# ospi143.net
KiCad netlist of a schematic drawn in EAGLE
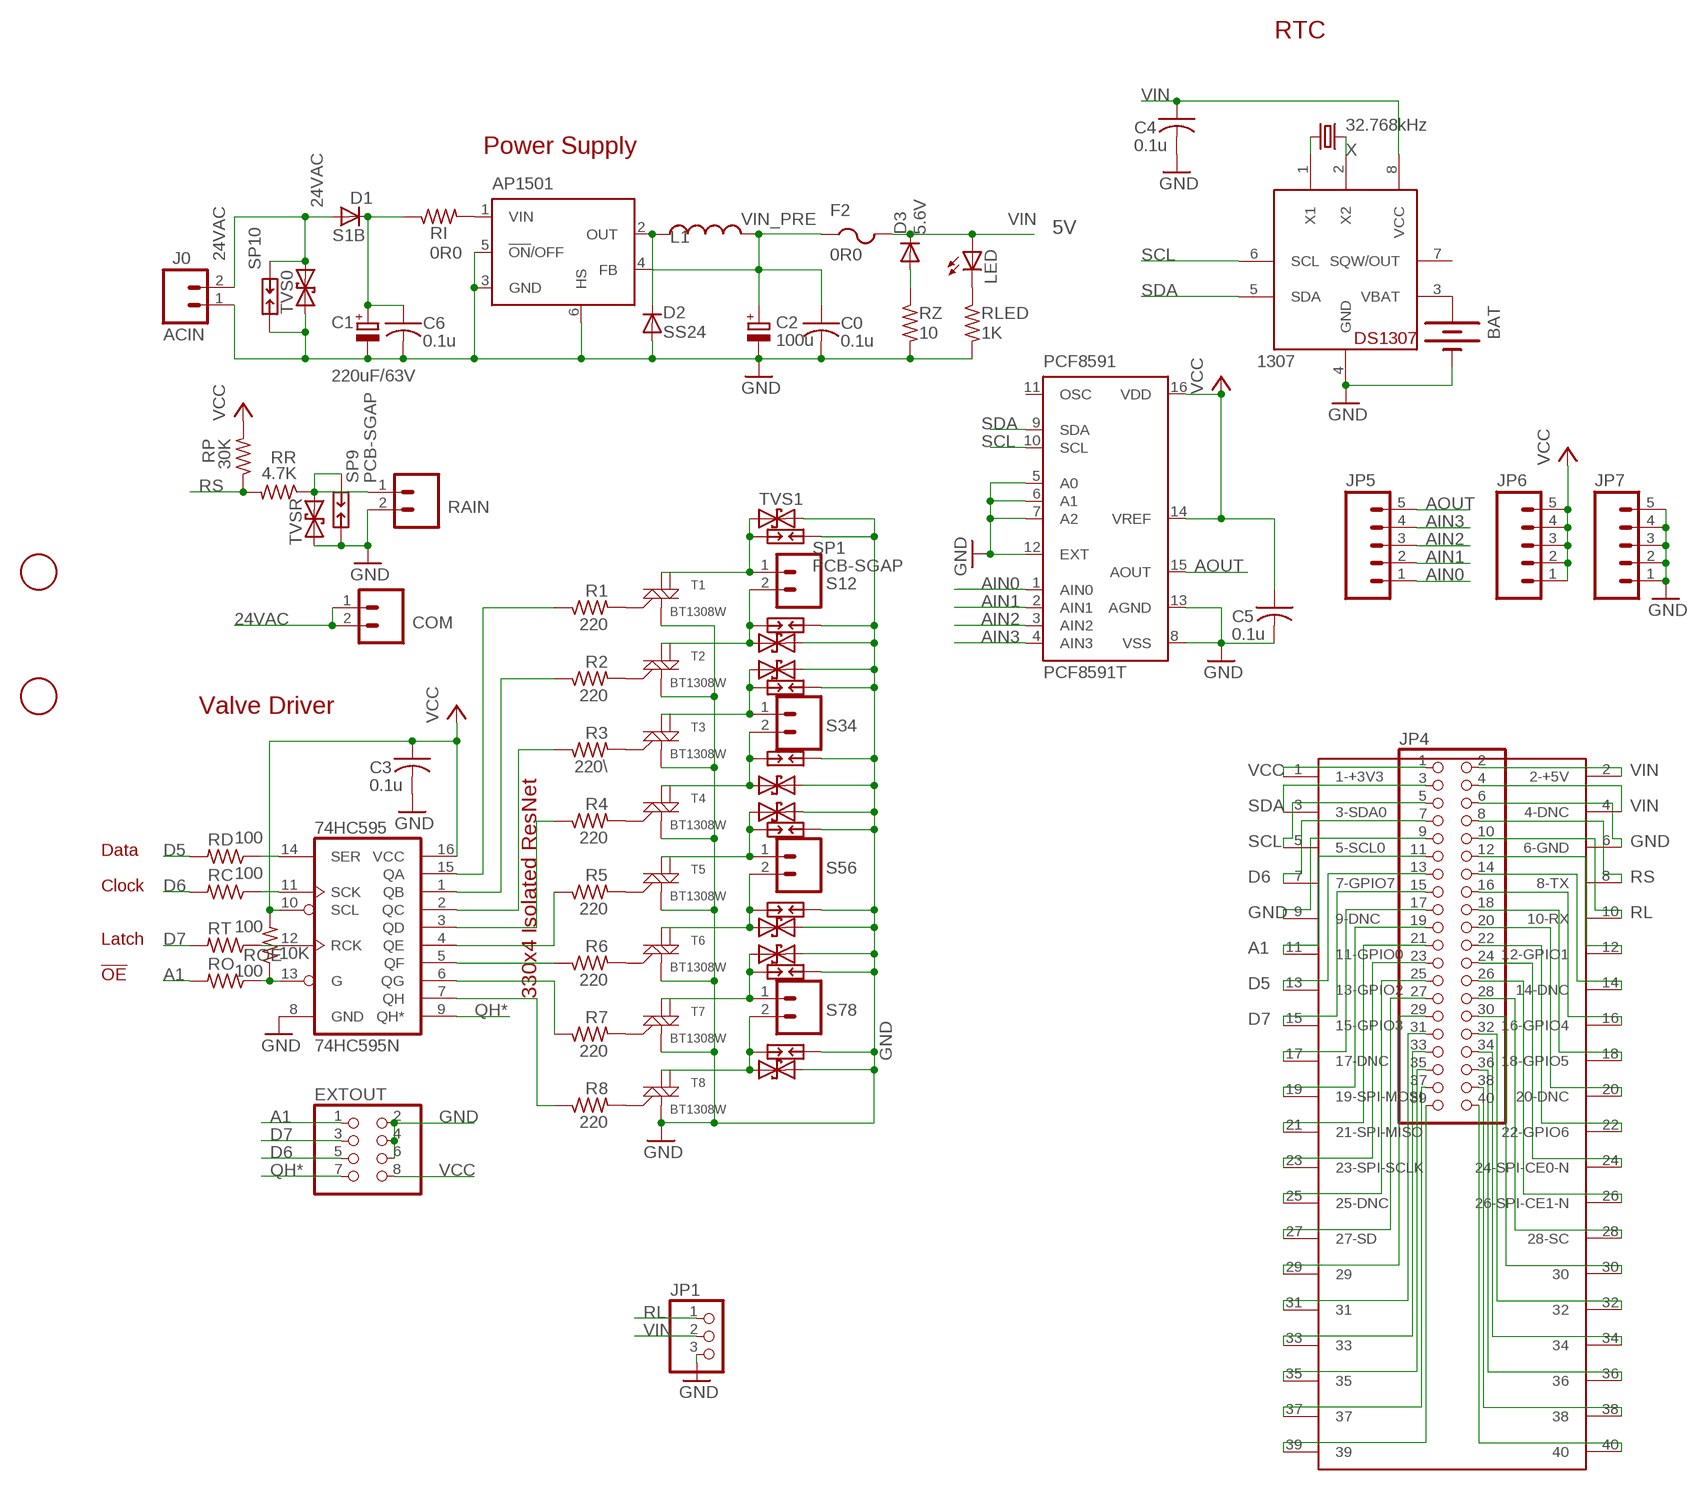
[diagram p0: schematic, sheet 1]

(export (version "E")
  (design (tool "Eeschema 10.0.6"))
  (components
    (comp (ref "74HC595")
      (value "74HC595N")
      (footprint "eagle-import:SO16")
      (libsource (lib "eagle-import") (part "74595DLS"))
    )
    (comp (ref "1307")
      (value "DS1307")
      (footprint "eagle-import:SO08")
      (libsource (lib "eagle-import") (part "DS1307SOIC"))
    )
    (comp (ref "AP1501")
      (value "LM2596S")
      (footprint "eagle-import:TO263-5")
      (fields (field (name "MF") "NATIONAL SEMICONDUCTOR") (field (name "MPN") "LM2596S-ADJ/NOPB"))
      (libsource (lib "eagle-import") (part "LM2596S"))
    )
    (comp (ref "BAT")
      (value "BATTERYBATTERY_12MM_SMT")
      (footprint "eagle-import:BATTCON_12MM_SMT")
      (libsource (lib "eagle-import") (part "BATTERYBATTERY_12MM_SMT"))
    )
    (comp (ref "C0")
      (value "0.1u")
      (footprint "eagle-import:C0603K")
      (libsource (lib "eagle-import") (part "C-USC0603K"))
    )
    (comp (ref "C1")
      (value "220uF/63V")
      (footprint "eagle-import:PANASONIC_E")
      (libsource (lib "eagle-import") (part "CPOL-EUE"))
    )
    (comp (ref "C2")
      (value "100u")
      (footprint "eagle-import:PANASONIC_E")
      (libsource (lib "eagle-import") (part "CPOL-EUE"))
    )
    (comp (ref "C3")
      (value "0.1u")
      (footprint "eagle-import:C0603K")
      (libsource (lib "eagle-import") (part "C-USC0603K"))
    )
    (comp (ref "C4")
      (value "0.1u")
      (footprint "eagle-import:C0603K")
      (libsource (lib "eagle-import") (part "C-USC0603K"))
    )
    (comp (ref "C5")
      (value "0.1u")
      (footprint "eagle-import:C0603K")
      (libsource (lib "eagle-import") (part "C-USC0603K"))
    )
    (comp (ref "C6")
      (value "0.1u")
      (footprint "eagle-import:C0603K")
      (libsource (lib "eagle-import") (part "C-USC0603K"))
    )
    (comp (ref "COM")
      (value "M025MM-X")
      (footprint "eagle-import:SCREWTERMINAL-5MM-2-X")
      (libsource (lib "eagle-import") (part "M025MM-X"))
    )
    (comp (ref "D1")
      (value "S1B")
      (footprint "eagle-import:DO-214AC")
      (libsource (lib "eagle-import") (part "DIODE-DO-214AC"))
    )
    (comp (ref "D2")
      (value "SS24")
      (footprint "eagle-import:SMB")
      (libsource (lib "eagle-import") (part "DIODE-SMB"))
    )
    (comp (ref "D3")
      (value "5.6V")
      (footprint "eagle-import:MINIMELF")
      (libsource (lib "eagle-import") (part "DIODE-MINIMELF"))
    )
    (comp (ref "EXTOUT")
      (value "PINHD-2X4/90")
      (footprint "eagle-import:2X04_90")
      (libsource (lib "eagle-import") (part "PINHD-2X4/90"))
    )
    (comp (ref "F2")
      (value "0R0")
      (footprint "eagle-import:1812")
      (libsource (lib "eagle-import") (part "PTCFUSE-1812"))
    )
    (comp (ref "J0")
      (value "ACIN")
      (footprint "eagle-import:SCREWTERMINAL-4MM-2-X")
      (libsource (lib "eagle-import") (part "M024MM-X"))
    )
    (comp (ref "JP1")
      (value "PINHD-1X3")
      (footprint "eagle-import:1X03")
      (libsource (lib "eagle-import") (part "PINHD-1X3"))
    )
    (comp (ref "JP4")
      (value "PINHD-2X20")
      (footprint "eagle-import:2X20")
      (libsource (lib "eagle-import") (part "PINHD-2X20"))
    )
    (comp (ref "JP5")
      (value "M05PTH")
      (footprint "eagle-import:1X05")
      (libsource (lib "eagle-import") (part "M05PTH"))
    )
    (comp (ref "JP6")
      (value "M05PTH")
      (footprint "eagle-import:1X05")
      (libsource (lib "eagle-import") (part "M05PTH"))
    )
    (comp (ref "JP7")
      (value "M05PTH")
      (footprint "eagle-import:1X05")
      (libsource (lib "eagle-import") (part "M05PTH"))
    )
    (comp (ref "L1")
      (value "150uH")
      (footprint "eagle-import:CDRH125")
      (libsource (lib "eagle-import") (part "INDUCTORPWR"))
    )
    (comp (ref "LED")
      (value "LEDCHIPLED_0805")
      (footprint "eagle-import:CHIPLED_0805")
      (libsource (lib "eagle-import") (part "LEDCHIPLED_0805"))
    )
    (comp (ref "PCF8591")
      (value "PCF8591T")
      (footprint "eagle-import:SO16W")
      (fields (field (name "MPN") "PCF8591T/2,512"))
      (libsource (lib "eagle-import") (part "PCF8591T"))
    )
    (comp (ref "R1")
      (value "220")
      (footprint "eagle-import:R0603")
      (libsource (lib "eagle-import") (part "R-US_R0603"))
    )
    (comp (ref "R2")
      (value "220")
      (footprint "eagle-import:R0603")
      (libsource (lib "eagle-import") (part "R-US_R0603"))
    )
    (comp (ref "R3")
      (value "220\\")
      (footprint "eagle-import:R0603")
      (libsource (lib "eagle-import") (part "R-US_R0603"))
    )
    (comp (ref "R4")
      (value "220")
      (footprint "eagle-import:R0603")
      (libsource (lib "eagle-import") (part "R-US_R0603"))
    )
    (comp (ref "R5")
      (value "220")
      (footprint "eagle-import:R0603")
      (libsource (lib "eagle-import") (part "R-US_R0603"))
    )
    (comp (ref "R6")
      (value "220")
      (footprint "eagle-import:R0603")
      (libsource (lib "eagle-import") (part "R-US_R0603"))
    )
    (comp (ref "R7")
      (value "220")
      (footprint "eagle-import:R0603")
      (libsource (lib "eagle-import") (part "R-US_R0603"))
    )
    (comp (ref "R8")
      (value "220")
      (footprint "eagle-import:R0603")
      (libsource (lib "eagle-import") (part "R-US_R0603"))
    )
    (comp (ref "RAIN")
      (value "M025MM-X")
      (footprint "eagle-import:SCREWTERMINAL-5MM-2-X")
      (libsource (lib "eagle-import") (part "M025MM-X"))
    )
    (comp (ref "RC")
      (value "100")
      (footprint "eagle-import:R0603")
      (libsource (lib "eagle-import") (part "R-US_R0603"))
    )
    (comp (ref "RD")
      (value "100")
      (footprint "eagle-import:R0603")
      (libsource (lib "eagle-import") (part "R-US_R0603"))
    )
    (comp (ref "RI")
      (value "0R0")
      (footprint "eagle-import:R2010")
      (libsource (lib "eagle-import") (part "adafruitGood_R-US_R2010"))
    )
    (comp (ref "RLED")
      (value "1K")
      (footprint "eagle-import:R0805")
      (libsource (lib "eagle-import") (part "R-US_R0805"))
    )
    (comp (ref "RO")
      (value "100")
      (footprint "eagle-import:R0603")
      (libsource (lib "eagle-import") (part "R-US_R0603"))
    )
    (comp (ref "ROE")
      (value "10K")
      (footprint "eagle-import:R0603")
      (libsource (lib "eagle-import") (part "R-US_R0603"))
    )
    (comp (ref "RP")
      (value "30K")
      (footprint "eagle-import:R0805")
      (libsource (lib "eagle-import") (part "R-US_R0805"))
    )
    (comp (ref "RR")
      (value "4.7K")
      (footprint "eagle-import:R0805")
      (libsource (lib "eagle-import") (part "R-US_R0805"))
    )
    (comp (ref "RT")
      (value "100")
      (footprint "eagle-import:R0603")
      (libsource (lib "eagle-import") (part "R-US_R0603"))
    )
    (comp (ref "RZ")
      (value "10")
      (footprint "eagle-import:R2010")
      (libsource (lib "eagle-import") (part "R-US_R2010"))
    )
    (comp (ref "S12")
      (value "M025MM-X")
      (footprint "eagle-import:SCREWTERMINAL-5MM-2-X")
      (libsource (lib "eagle-import") (part "M025MM-X"))
    )
    (comp (ref "S34")
      (value "M025MM-X")
      (footprint "eagle-import:SCREWTERMINAL-5MM-2-X")
      (libsource (lib "eagle-import") (part "M025MM-X"))
    )
    (comp (ref "S56")
      (value "M025MM-X")
      (footprint "eagle-import:SCREWTERMINAL-5MM-2-X")
      (libsource (lib "eagle-import") (part "M025MM-X"))
    )
    (comp (ref "S78")
      (value "M025MM-X")
      (footprint "eagle-import:SCREWTERMINAL-5MM-2-X")
      (libsource (lib "eagle-import") (part "M025MM-X"))
    )
    (comp (ref "SP1")
      (value "PCB-SGAP")
      (footprint "eagle-import:PCB-SGAP")
      (libsource (lib "eagle-import") (part "PCB-SGAP"))
    )
    (comp (ref "SP2")
      (value "PCB-SGAP")
      (footprint "eagle-import:PCB-SGAP")
      (libsource (lib "eagle-import") (part "PCB-SGAP"))
    )
    (comp (ref "SP3")
      (value "PCB-SGAP")
      (footprint "eagle-import:PCB-SGAP")
      (libsource (lib "eagle-import") (part "PCB-SGAP"))
    )
    (comp (ref "SP4")
      (value "PCB-SGAP")
      (footprint "eagle-import:PCB-SGAP")
      (libsource (lib "eagle-import") (part "PCB-SGAP"))
    )
    (comp (ref "SP5")
      (value "PCB-SGAP")
      (footprint "eagle-import:PCB-SGAP")
      (libsource (lib "eagle-import") (part "PCB-SGAP"))
    )
    (comp (ref "SP6")
      (value "PCB-SGAP")
      (footprint "eagle-import:PCB-SGAP")
      (libsource (lib "eagle-import") (part "PCB-SGAP"))
    )
    (comp (ref "SP7")
      (value "PCB-SGAP")
      (footprint "eagle-import:PCB-SGAP")
      (libsource (lib "eagle-import") (part "PCB-SGAP"))
    )
    (comp (ref "SP8")
      (value "PCB-SGAP")
      (footprint "eagle-import:PCB-SGAP")
      (libsource (lib "eagle-import") (part "PCB-SGAP"))
    )
    (comp (ref "SP9")
      (value "PCB-SGAP")
      (footprint "eagle-import:PCB-SGAP")
      (libsource (lib "eagle-import") (part "PCB-SGAP"))
    )
    (comp (ref "SP10")
      (value "PCB-SGAP")
      (footprint "eagle-import:PCB-SGAP")
      (libsource (lib "eagle-import") (part "PCB-SGAP"))
    )
    (comp (ref "T1")
      (value "BT1308W")
      (footprint "eagle-import:SOT223")
      (libsource (lib "eagle-import") (part "MAC97SOT223"))
    )
    (comp (ref "T2")
      (value "BT1308W")
      (footprint "eagle-import:SOT223")
      (libsource (lib "eagle-import") (part "MAC97SOT223"))
    )
    (comp (ref "T3")
      (value "BT1308W")
      (footprint "eagle-import:SOT223")
      (libsource (lib "eagle-import") (part "MAC97SOT223"))
    )
    (comp (ref "T4")
      (value "BT1308W")
      (footprint "eagle-import:SOT223")
      (libsource (lib "eagle-import") (part "MAC97SOT223"))
    )
    (comp (ref "T5")
      (value "BT1308W")
      (footprint "eagle-import:SOT223")
      (libsource (lib "eagle-import") (part "MAC97SOT223"))
    )
    (comp (ref "T6")
      (value "BT1308W")
      (footprint "eagle-import:SOT223")
      (libsource (lib "eagle-import") (part "MAC97SOT223"))
    )
    (comp (ref "T7")
      (value "BT1308W")
      (footprint "eagle-import:SOT223")
      (libsource (lib "eagle-import") (part "MAC97SOT223"))
    )
    (comp (ref "T8")
      (value "BT1308W")
      (footprint "eagle-import:SOT223")
      (libsource (lib "eagle-import") (part "MAC97SOT223"))
    )
    (comp (ref "TVS0")
      (value "TVSSMB")
      (footprint "eagle-import:SMB")
      (libsource (lib "eagle-import") (part "TVSSMB"))
    )
    (comp (ref "TVS1")
      (value "TVSSMB")
      (footprint "eagle-import:SMB")
      (libsource (lib "eagle-import") (part "TVSSMB"))
    )
    (comp (ref "TVS2")
      (value "TVSSMB")
      (footprint "eagle-import:SMB")
      (libsource (lib "eagle-import") (part "TVSSMB"))
    )
    (comp (ref "TVS3")
      (value "TVSSMB")
      (footprint "eagle-import:SMB")
      (libsource (lib "eagle-import") (part "TVSSMB"))
    )
    (comp (ref "TVS4")
      (value "TVSSMB")
      (footprint "eagle-import:SMB")
      (libsource (lib "eagle-import") (part "TVSSMB"))
    )
    (comp (ref "TVS5")
      (value "TVSSMB")
      (footprint "eagle-import:SMB")
      (libsource (lib "eagle-import") (part "TVSSMB"))
    )
    (comp (ref "TVS6")
      (value "TVSSMB")
      (footprint "eagle-import:SMB")
      (libsource (lib "eagle-import") (part "TVSSMB"))
    )
    (comp (ref "TVS7")
      (value "TVSSMB")
      (footprint "eagle-import:SMB")
      (libsource (lib "eagle-import") (part "TVSSMB"))
    )
    (comp (ref "TVS8")
      (value "TVSSMB")
      (footprint "eagle-import:SMB")
      (libsource (lib "eagle-import") (part "TVSSMB"))
    )
    (comp (ref "TVSR")
      (value "TVSSMB")
      (footprint "eagle-import:SMB")
      (libsource (lib "eagle-import") (part "TVSSMB"))
    )
    (comp (ref "U$1")
      (value "FIDUCIAL")
      (footprint "eagle-import:FIDUCIAL_1MM")
      (libsource (lib "eagle-import") (part "FIDUCIAL"))
    )
    (comp (ref "U$2")
      (value "RPIB+")
      (footprint "eagle-import:RPIB+")
      (libsource (lib "eagle-import") (part "RPIB+"))
    )
    (comp (ref "U$3")
      (value "FIDUCIAL")
      (footprint "eagle-import:FIDUCIAL_1MM")
      (libsource (lib "eagle-import") (part "FIDUCIAL"))
    )
    (comp (ref "X")
      (value "32.768kHz")
      (footprint "eagle-import:MM20SS")
      (libsource (lib "eagle-import") (part "CRYSTALMM20SS"))
    )
  )
  (nets
    (net (code "1") (name "/24VAC") (class "Default")
      (node (ref "COM") (pin "1") (pinfunction "1_1") (pintype "passive"))
      (node (ref "COM") (pin "2") (pinfunction "2_2") (pintype "passive"))
      (node (ref "D1") (pin "A") (pinfunction "A_A") (pintype "passive"))
      (node (ref "J0") (pin "2") (pinfunction "2_2") (pintype "passive"))
      (node (ref "SP10") (pin "1") (pinfunction "1_1") (pintype "passive"))
      (node (ref "TVS0") (pin "C") (pinfunction "C_C") (pintype "passive"))
    )
    (net (code "2") (name "/A1") (class "Default")
      (node (ref "EXTOUT") (pin "1") (pinfunction "1_1") (pintype "passive"))
      (node (ref "JP4") (pin "11") (pinfunction "11_11") (pintype "passive"))
      (node (ref "RO") (pin "2") (pinfunction "2_2") (pintype "passive"))
      (node (ref "U$2") (pin "11") (pinfunction "11-GPIO0_11") (pintype "bidirectional"))
    )
    (net (code "3") (name "/AIN0") (class "Default")
      (node (ref "JP5") (pin "1") (pinfunction "1_1") (pintype "passive"))
      (node (ref "PCF8591") (pin "1") (pinfunction "AIN0_1") (pintype "input"))
    )
    (net (code "4") (name "/AIN1") (class "Default")
      (node (ref "JP5") (pin "2") (pinfunction "2_2") (pintype "passive"))
      (node (ref "PCF8591") (pin "2") (pinfunction "AIN1_2") (pintype "input"))
    )
    (net (code "5") (name "/AIN2") (class "Default")
      (node (ref "JP5") (pin "3") (pinfunction "3_3") (pintype "passive"))
      (node (ref "PCF8591") (pin "3") (pinfunction "AIN2_3") (pintype "input"))
    )
    (net (code "6") (name "/AIN3") (class "Default")
      (node (ref "JP5") (pin "4") (pinfunction "4_4") (pintype "passive"))
      (node (ref "PCF8591") (pin "4") (pinfunction "AIN3_4") (pintype "input"))
    )
    (net (code "7") (name "/AOUT") (class "Default")
      (node (ref "JP5") (pin "5") (pinfunction "5_5") (pintype "passive"))
      (node (ref "PCF8591") (pin "15") (pinfunction "AOUT_15") (pintype "output"))
    )
    (net (code "8") (name "/D5") (class "Default")
      (node (ref "JP4") (pin "13") (pinfunction "13_13") (pintype "passive"))
      (node (ref "RD") (pin "2") (pinfunction "2_2") (pintype "passive"))
      (node (ref "U$2") (pin "13") (pinfunction "13-GPIO2_13") (pintype "bidirectional"))
    )
    (net (code "9") (name "/D6") (class "Default")
      (node (ref "EXTOUT") (pin "5") (pinfunction "5_5") (pintype "passive"))
      (node (ref "JP4") (pin "7") (pinfunction "7_7") (pintype "passive"))
      (node (ref "RC") (pin "2") (pinfunction "2_2") (pintype "passive"))
      (node (ref "U$2") (pin "7") (pinfunction "7-GPIO7_7") (pintype "bidirectional"))
    )
    (net (code "10") (name "/D7") (class "Default")
      (node (ref "EXTOUT") (pin "3") (pinfunction "3_3") (pintype "passive"))
      (node (ref "JP4") (pin "15") (pinfunction "15_15") (pintype "passive"))
      (node (ref "RT") (pin "2") (pinfunction "2_2") (pintype "passive"))
      (node (ref "U$2") (pin "15") (pinfunction "15-GPIO3_15") (pintype "bidirectional"))
    )
    (net (code "11") (name "/QH*") (class "Default")
      (node (ref "74HC595") (pin "9") (pinfunction "QH*_9") (pintype "tri_state"))
      (node (ref "EXTOUT") (pin "7") (pinfunction "7_7") (pintype "passive"))
    )
    (net (code "12") (name "/RL") (class "Default")
      (node (ref "JP1") (pin "1") (pinfunction "1_1") (pintype "passive"))
      (node (ref "JP4") (pin "10") (pinfunction "10_10") (pintype "passive"))
      (node (ref "U$2") (pin "10") (pinfunction "10-RX_10") (pintype "bidirectional"))
    )
    (net (code "13") (name "/RS") (class "Default")
      (node (ref "JP4") (pin "8") (pinfunction "8_8") (pintype "passive"))
      (node (ref "RP") (pin "1") (pinfunction "1_1") (pintype "passive"))
      (node (ref "RR") (pin "2") (pinfunction "2_2") (pintype "passive"))
      (node (ref "U$2") (pin "8") (pinfunction "8-TX_8") (pintype "bidirectional"))
    )
    (net (code "14") (name "/SCL") (class "Default")
      (node (ref "1307") (pin "6") (pinfunction "SCL_6") (pintype "bidirectional"))
      (node (ref "JP4") (pin "5") (pinfunction "5_5") (pintype "passive"))
      (node (ref "PCF8591") (pin "10") (pinfunction "SCL_10") (pintype "input"))
      (node (ref "U$2") (pin "5") (pinfunction "5-SCL0_5") (pintype "bidirectional"))
    )
    (net (code "15") (name "/SDA") (class "Default")
      (node (ref "1307") (pin "5") (pinfunction "SDA_5") (pintype "bidirectional"))
      (node (ref "JP4") (pin "3") (pinfunction "3_3") (pintype "passive"))
      (node (ref "PCF8591") (pin "9") (pinfunction "SDA_9") (pintype "bidirectional"))
      (node (ref "U$2") (pin "3") (pinfunction "3-SDA0_3") (pintype "bidirectional"))
    )
    (net (code "16") (name "/VIN") (class "Default")
      (node (ref "1307") (pin "8") (pinfunction "VCC_8") (pintype "power_in"))
      (node (ref "C4") (pin "1") (pinfunction "1_1") (pintype "passive"))
      (node (ref "D3") (pin "C") (pinfunction "C_C") (pintype "passive"))
      (node (ref "F2") (pin "2") (pinfunction "2_2") (pintype "passive"))
      (node (ref "JP1") (pin "2") (pinfunction "2_2") (pintype "passive"))
      (node (ref "JP4") (pin "2") (pinfunction "2_2") (pintype "passive"))
      (node (ref "JP4") (pin "4") (pinfunction "4_4") (pintype "passive"))
      (node (ref "LED") (pin "A") (pinfunction "A_A") (pintype "passive"))
      (node (ref "U$2") (pin "2") (pinfunction "2-+5V_2") (pintype "bidirectional"))
      (node (ref "U$2") (pin "4") (pinfunction "4-DNC_4") (pintype "bidirectional"))
    )
    (net (code "17") (name "/VIN_PRE") (class "Default")
      (node (ref "AP1501") (pin "4") (pinfunction "FB_4") (pintype "input"))
      (node (ref "C0") (pin "1") (pinfunction "1_1") (pintype "passive"))
      (node (ref "C2") (pin "+") (pinfunction "+_+") (pintype "passive"))
      (node (ref "F2") (pin "1") (pinfunction "1_1") (pintype "passive"))
      (node (ref "L1") (pin "2") (pinfunction "2_2") (pintype "passive"))
    )
    (net (code "18") (name "GND") (class "Default")
      (node (ref "1307") (pin "4") (pinfunction "GND_4") (pintype "power_in"))
      (node (ref "74HC595") (pin "8") (pinfunction "GND_8") (pintype "power_in"))
      (node (ref "AP1501") (pin "3") (pinfunction "GND_3") (pintype "power_in"))
      (node (ref "AP1501") (pin "5") (pinfunction "~{ON}/OFF_5") (pintype "input"))
      (node (ref "AP1501") (pin "6") (pinfunction "HS_6") (pintype "power_in"))
      (node (ref "BAT") (pin "P$1") (pinfunction "-_P$1") (pintype "power_in"))
      (node (ref "C0") (pin "2") (pinfunction "2_2") (pintype "passive"))
      (node (ref "C1") (pin "-") (pinfunction "-_-") (pintype "passive"))
      (node (ref "C2") (pin "-") (pinfunction "-_-") (pintype "passive"))
      (node (ref "C3") (pin "2") (pinfunction "2_2") (pintype "passive"))
      (node (ref "C4") (pin "2") (pinfunction "2_2") (pintype "passive"))
      (node (ref "C5") (pin "2") (pinfunction "2_2") (pintype "passive"))
      (node (ref "C6") (pin "2") (pinfunction "2_2") (pintype "passive"))
      (node (ref "D2") (pin "A") (pinfunction "A_A") (pintype "passive"))
      (node (ref "EXTOUT") (pin "2") (pinfunction "2_2") (pintype "passive"))
      (node (ref "EXTOUT") (pin "4") (pinfunction "4_4") (pintype "passive"))
      (node (ref "EXTOUT") (pin "6") (pinfunction "6_6") (pintype "passive"))
      (node (ref "J0") (pin "1") (pinfunction "1_1") (pintype "passive"))
      (node (ref "JP1") (pin "3") (pinfunction "3_3") (pintype "passive"))
      (node (ref "JP4") (pin "6") (pinfunction "6_6") (pintype "passive"))
      (node (ref "JP4") (pin "9") (pinfunction "9_9") (pintype "passive"))
      (node (ref "JP7") (pin "1") (pinfunction "1_1") (pintype "passive"))
      (node (ref "JP7") (pin "2") (pinfunction "2_2") (pintype "passive"))
      (node (ref "JP7") (pin "3") (pinfunction "3_3") (pintype "passive"))
      (node (ref "JP7") (pin "4") (pinfunction "4_4") (pintype "passive"))
      (node (ref "JP7") (pin "5") (pinfunction "5_5") (pintype "passive"))
      (node (ref "PCF8591") (pin "12") (pinfunction "EXT_12") (pintype "input"))
      (node (ref "PCF8591") (pin "13") (pinfunction "AGND_13") (pintype "power_in"))
      (node (ref "PCF8591") (pin "5") (pinfunction "A0_5") (pintype "input"))
      (node (ref "PCF8591") (pin "6") (pinfunction "A1_6") (pintype "input"))
      (node (ref "PCF8591") (pin "7") (pinfunction "A2_7") (pintype "input"))
      (node (ref "PCF8591") (pin "8") (pinfunction "VSS_8") (pintype "power_in"))
      (node (ref "RAIN") (pin "2") (pinfunction "2_2") (pintype "passive"))
      (node (ref "RLED") (pin "2") (pinfunction "2_2") (pintype "passive"))
      (node (ref "RZ") (pin "2") (pinfunction "2_2") (pintype "passive"))
      (node (ref "SP1") (pin "1") (pinfunction "1_1") (pintype "passive"))
      (node (ref "SP10") (pin "2") (pinfunction "2_2") (pintype "passive"))
      (node (ref "SP2") (pin "1") (pinfunction "1_1") (pintype "passive"))
      (node (ref "SP3") (pin "1") (pinfunction "1_1") (pintype "passive"))
      (node (ref "SP4") (pin "1") (pinfunction "1_1") (pintype "passive"))
      (node (ref "SP5") (pin "1") (pinfunction "1_1") (pintype "passive"))
      (node (ref "SP6") (pin "1") (pinfunction "1_1") (pintype "passive"))
      (node (ref "SP7") (pin "1") (pinfunction "1_1") (pintype "passive"))
      (node (ref "SP8") (pin "1") (pinfunction "1_1") (pintype "passive"))
      (node (ref "SP9") (pin "2") (pinfunction "2_2") (pintype "passive"))
      (node (ref "T1") (pin "1") (pinfunction "M1_1") (pintype "bidirectional"))
      (node (ref "T2") (pin "1") (pinfunction "M1_1") (pintype "bidirectional"))
      (node (ref "T3") (pin "1") (pinfunction "M1_1") (pintype "bidirectional"))
      (node (ref "T4") (pin "1") (pinfunction "M1_1") (pintype "bidirectional"))
      (node (ref "T5") (pin "1") (pinfunction "M1_1") (pintype "bidirectional"))
      (node (ref "T6") (pin "1") (pinfunction "M1_1") (pintype "bidirectional"))
      (node (ref "T7") (pin "1") (pinfunction "M1_1") (pintype "bidirectional"))
      (node (ref "T8") (pin "1") (pinfunction "M1_1") (pintype "bidirectional"))
      (node (ref "TVS0") (pin "A") (pinfunction "A_A") (pintype "passive"))
      (node (ref "TVS1") (pin "C") (pinfunction "C_C") (pintype "passive"))
      (node (ref "TVS2") (pin "C") (pinfunction "C_C") (pintype "passive"))
      (node (ref "TVS3") (pin "C") (pinfunction "C_C") (pintype "passive"))
      (node (ref "TVS4") (pin "C") (pinfunction "C_C") (pintype "passive"))
      (node (ref "TVS5") (pin "C") (pinfunction "C_C") (pintype "passive"))
      (node (ref "TVS6") (pin "C") (pinfunction "C_C") (pintype "passive"))
      (node (ref "TVS7") (pin "C") (pinfunction "C_C") (pintype "passive"))
      (node (ref "TVS8") (pin "C") (pinfunction "C_C") (pintype "passive"))
      (node (ref "TVSR") (pin "A") (pinfunction "A_A") (pintype "passive"))
      (node (ref "U$2") (pin "6") (pinfunction "6-GND_6") (pintype "bidirectional"))
      (node (ref "U$2") (pin "9") (pinfunction "9-DNC_9") (pintype "bidirectional"))
    )
    (net (code "19") (name "Net-(74HC595-G)") (class "Default")
      (node (ref "74HC595") (pin "13") (pinfunction "G_13") (pintype "input"))
      (node (ref "RO") (pin "1") (pinfunction "1_1") (pintype "passive"))
      (node (ref "ROE") (pin "1") (pinfunction "1_1") (pintype "passive"))
    )
    (net (code "20") (name "Net-(74HC595-QA)") (class "Default")
      (node (ref "74HC595") (pin "15") (pinfunction "QA_15") (pintype "tri_state"))
      (node (ref "R1") (pin "1") (pinfunction "1_1") (pintype "passive"))
    )
    (net (code "21") (name "Net-(74HC595-QB)") (class "Default")
      (node (ref "74HC595") (pin "1") (pinfunction "QB_1") (pintype "tri_state"))
      (node (ref "R2") (pin "1") (pinfunction "1_1") (pintype "passive"))
    )
    (net (code "22") (name "Net-(74HC595-QC)") (class "Default")
      (node (ref "74HC595") (pin "2") (pinfunction "QC_2") (pintype "tri_state"))
      (node (ref "R3") (pin "1") (pinfunction "1_1") (pintype "passive"))
    )
    (net (code "23") (name "Net-(74HC595-QD)") (class "Default")
      (node (ref "74HC595") (pin "3") (pinfunction "QD_3") (pintype "tri_state"))
      (node (ref "R4") (pin "1") (pinfunction "1_1") (pintype "passive"))
    )
    (net (code "24") (name "Net-(74HC595-QE)") (class "Default")
      (node (ref "74HC595") (pin "4") (pinfunction "QE_4") (pintype "tri_state"))
      (node (ref "R5") (pin "1") (pinfunction "1_1") (pintype "passive"))
    )
    (net (code "25") (name "Net-(74HC595-QF)") (class "Default")
      (node (ref "74HC595") (pin "5") (pinfunction "QF_5") (pintype "tri_state"))
      (node (ref "R6") (pin "1") (pinfunction "1_1") (pintype "passive"))
    )
    (net (code "26") (name "Net-(74HC595-QG)") (class "Default")
      (node (ref "74HC595") (pin "6") (pinfunction "QG_6") (pintype "tri_state"))
      (node (ref "R7") (pin "1") (pinfunction "1_1") (pintype "passive"))
    )
    (net (code "27") (name "Net-(74HC595-QH)") (class "Default")
      (node (ref "74HC595") (pin "7") (pinfunction "QH_7") (pintype "tri_state"))
      (node (ref "R8") (pin "1") (pinfunction "1_1") (pintype "passive"))
    )
    (net (code "28") (name "Net-(74HC595-RCK)") (class "Default")
      (node (ref "74HC595") (pin "12") (pinfunction "RCK_12") (pintype "input"))
      (node (ref "RT") (pin "1") (pinfunction "1_1") (pintype "passive"))
    )
    (net (code "29") (name "Net-(74HC595-SCK)") (class "Default")
      (node (ref "74HC595") (pin "11") (pinfunction "SCK_11") (pintype "input"))
      (node (ref "RC") (pin "1") (pinfunction "1_1") (pintype "passive"))
    )
    (net (code "30") (name "Net-(74HC595-SER)") (class "Default")
      (node (ref "74HC595") (pin "14") (pinfunction "SER_14") (pintype "input"))
      (node (ref "RD") (pin "1") (pinfunction "1_1") (pintype "passive"))
    )
    (net (code "31") (name "Net-(1307-VBAT)") (class "Default")
      (node (ref "1307") (pin "3") (pinfunction "VBAT_3") (pintype "power_in"))
      (node (ref "BAT") (pin "P$2") (pinfunction "+_P$2") (pintype "power_in"))
    )
    (net (code "32") (name "Net-(1307-X1)") (class "Default")
      (node (ref "1307") (pin "1") (pinfunction "X1_1") (pintype "passive"))
      (node (ref "X") (pin "1") (pinfunction "1_1") (pintype "passive"))
    )
    (net (code "33") (name "Net-(1307-X2)") (class "Default")
      (node (ref "1307") (pin "2") (pinfunction "X2_2") (pintype "passive"))
      (node (ref "X") (pin "4") (pinfunction "2_4") (pintype "passive"))
    )
    (net (code "34") (name "Net-(AP1501-OUT)") (class "Default")
      (node (ref "AP1501") (pin "2") (pinfunction "OUT_2") (pintype "output"))
      (node (ref "D2") (pin "C") (pinfunction "C_C") (pintype "passive"))
      (node (ref "L1") (pin "1") (pinfunction "1_1") (pintype "passive"))
    )
    (net (code "35") (name "Net-(AP1501-VIN)") (class "Default")
      (node (ref "AP1501") (pin "1") (pinfunction "VIN_1") (pintype "input"))
      (node (ref "RI") (pin "2") (pinfunction "2_2") (pintype "passive"))
    )
    (net (code "36") (name "Net-(C1-Pad+)") (class "Default")
      (node (ref "C1") (pin "+") (pinfunction "+_+") (pintype "passive"))
      (node (ref "C6") (pin "1") (pinfunction "1_1") (pintype "passive"))
      (node (ref "D1") (pin "C") (pinfunction "C_C") (pintype "passive"))
      (node (ref "RI") (pin "1") (pinfunction "1_1") (pintype "passive"))
    )
    (net (code "37") (name "Net-(D3-PadA)") (class "Default")
      (node (ref "D3") (pin "A") (pinfunction "A_A") (pintype "passive"))
      (node (ref "RZ") (pin "1") (pinfunction "1_1") (pintype "passive"))
    )
    (net (code "38") (name "Net-(JP4-Pad29)") (class "Default")
      (node (ref "JP4") (pin "29") (pinfunction "29_29") (pintype "passive"))
      (node (ref "U$2") (pin "29") (pinfunction "29_29") (pintype "bidirectional"))
    )
    (net (code "39") (name "Net-(JP4-Pad30)") (class "Default")
      (node (ref "JP4") (pin "30") (pinfunction "30_30") (pintype "passive"))
      (node (ref "U$2") (pin "30") (pinfunction "30_30") (pintype "bidirectional"))
    )
    (net (code "40") (name "Net-(JP4-Pad31)") (class "Default")
      (node (ref "JP4") (pin "31") (pinfunction "31_31") (pintype "passive"))
      (node (ref "U$2") (pin "31") (pinfunction "31_31") (pintype "bidirectional"))
    )
    (net (code "41") (name "Net-(JP4-Pad32)") (class "Default")
      (node (ref "JP4") (pin "32") (pinfunction "32_32") (pintype "passive"))
      (node (ref "U$2") (pin "32") (pinfunction "32_32") (pintype "bidirectional"))
    )
    (net (code "42") (name "Net-(JP4-Pad33)") (class "Default")
      (node (ref "JP4") (pin "33") (pinfunction "33_33") (pintype "passive"))
      (node (ref "U$2") (pin "33") (pinfunction "33_33") (pintype "bidirectional"))
    )
    (net (code "43") (name "Net-(JP4-Pad34)") (class "Default")
      (node (ref "JP4") (pin "34") (pinfunction "34_34") (pintype "passive"))
      (node (ref "U$2") (pin "34") (pinfunction "34_34") (pintype "bidirectional"))
    )
    (net (code "44") (name "Net-(JP4-Pad35)") (class "Default")
      (node (ref "JP4") (pin "35") (pinfunction "35_35") (pintype "passive"))
      (node (ref "U$2") (pin "35") (pinfunction "35_35") (pintype "bidirectional"))
    )
    (net (code "45") (name "Net-(JP4-Pad36)") (class "Default")
      (node (ref "JP4") (pin "36") (pinfunction "36_36") (pintype "passive"))
      (node (ref "U$2") (pin "36") (pinfunction "36_36") (pintype "bidirectional"))
    )
    (net (code "46") (name "Net-(JP4-Pad37)") (class "Default")
      (node (ref "JP4") (pin "37") (pinfunction "37_37") (pintype "passive"))
      (node (ref "U$2") (pin "37") (pinfunction "37_37") (pintype "bidirectional"))
    )
    (net (code "47") (name "Net-(JP4-Pad38)") (class "Default")
      (node (ref "JP4") (pin "38") (pinfunction "38_38") (pintype "passive"))
      (node (ref "U$2") (pin "38") (pinfunction "38_38") (pintype "bidirectional"))
    )
    (net (code "48") (name "Net-(JP4-Pad39)") (class "Default")
      (node (ref "JP4") (pin "39") (pinfunction "39_39") (pintype "passive"))
      (node (ref "U$2") (pin "39") (pinfunction "39_39") (pintype "bidirectional"))
    )
    (net (code "49") (name "Net-(JP4-Pad40)") (class "Default")
      (node (ref "JP4") (pin "40") (pinfunction "40_40") (pintype "passive"))
      (node (ref "U$2") (pin "40") (pinfunction "40_40") (pintype "bidirectional"))
    )
    (net (code "50") (name "Net-(LED-PadC)") (class "Default")
      (node (ref "LED") (pin "C") (pinfunction "C_C") (pintype "passive"))
      (node (ref "RLED") (pin "1") (pinfunction "1_1") (pintype "passive"))
    )
    (net (code "51") (name "Net-(RAIN-Pad1)") (class "Default")
      (node (ref "RAIN") (pin "1") (pinfunction "1_1") (pintype "passive"))
      (node (ref "RR") (pin "1") (pinfunction "1_1") (pintype "passive"))
      (node (ref "SP9") (pin "1") (pinfunction "1_1") (pintype "passive"))
      (node (ref "TVSR") (pin "C") (pinfunction "C_C") (pintype "passive"))
    )
    (net (code "52") (name "Net-(T1-G)") (class "Default")
      (node (ref "R1") (pin "2") (pinfunction "2_2") (pintype "passive"))
      (node (ref "T1") (pin "3") (pinfunction "G_3") (pintype "bidirectional"))
    )
    (net (code "53") (name "Net-(T1-M2)") (class "Default")
      (node (ref "S12") (pin "1") (pinfunction "1_1") (pintype "passive"))
      (node (ref "SP1") (pin "2") (pinfunction "2_2") (pintype "passive"))
      (node (ref "T1") (pin "2") (pinfunction "M2_2") (pintype "bidirectional"))
      (node (ref "TVS1") (pin "A") (pinfunction "A_A") (pintype "passive"))
    )
    (net (code "54") (name "Net-(T2-G)") (class "Default")
      (node (ref "R2") (pin "2") (pinfunction "2_2") (pintype "passive"))
      (node (ref "T2") (pin "3") (pinfunction "G_3") (pintype "bidirectional"))
    )
    (net (code "55") (name "Net-(T2-M2)") (class "Default")
      (node (ref "S12") (pin "2") (pinfunction "2_2") (pintype "passive"))
      (node (ref "SP2") (pin "2") (pinfunction "2_2") (pintype "passive"))
      (node (ref "T2") (pin "2") (pinfunction "M2_2") (pintype "bidirectional"))
      (node (ref "TVS2") (pin "A") (pinfunction "A_A") (pintype "passive"))
    )
    (net (code "56") (name "Net-(T3-G)") (class "Default")
      (node (ref "R3") (pin "2") (pinfunction "2_2") (pintype "passive"))
      (node (ref "T3") (pin "3") (pinfunction "G_3") (pintype "bidirectional"))
    )
    (net (code "57") (name "Net-(T3-M2)") (class "Default")
      (node (ref "S34") (pin "1") (pinfunction "1_1") (pintype "passive"))
      (node (ref "SP3") (pin "2") (pinfunction "2_2") (pintype "passive"))
      (node (ref "T3") (pin "2") (pinfunction "M2_2") (pintype "bidirectional"))
      (node (ref "TVS3") (pin "A") (pinfunction "A_A") (pintype "passive"))
    )
    (net (code "58") (name "Net-(T4-G)") (class "Default")
      (node (ref "R4") (pin "2") (pinfunction "2_2") (pintype "passive"))
      (node (ref "T4") (pin "3") (pinfunction "G_3") (pintype "bidirectional"))
    )
    (net (code "59") (name "Net-(T4-M2)") (class "Default")
      (node (ref "S34") (pin "2") (pinfunction "2_2") (pintype "passive"))
      (node (ref "SP4") (pin "2") (pinfunction "2_2") (pintype "passive"))
      (node (ref "T4") (pin "2") (pinfunction "M2_2") (pintype "bidirectional"))
      (node (ref "TVS4") (pin "A") (pinfunction "A_A") (pintype "passive"))
    )
    (net (code "60") (name "Net-(T5-G)") (class "Default")
      (node (ref "R5") (pin "2") (pinfunction "2_2") (pintype "passive"))
      (node (ref "T5") (pin "3") (pinfunction "G_3") (pintype "bidirectional"))
    )
    (net (code "61") (name "Net-(T5-M2)") (class "Default")
      (node (ref "S56") (pin "1") (pinfunction "1_1") (pintype "passive"))
      (node (ref "SP5") (pin "2") (pinfunction "2_2") (pintype "passive"))
      (node (ref "T5") (pin "2") (pinfunction "M2_2") (pintype "bidirectional"))
      (node (ref "TVS5") (pin "A") (pinfunction "A_A") (pintype "passive"))
    )
    (net (code "62") (name "Net-(T6-G)") (class "Default")
      (node (ref "R6") (pin "2") (pinfunction "2_2") (pintype "passive"))
      (node (ref "T6") (pin "3") (pinfunction "G_3") (pintype "bidirectional"))
    )
    (net (code "63") (name "Net-(T6-M2)") (class "Default")
      (node (ref "S56") (pin "2") (pinfunction "2_2") (pintype "passive"))
      (node (ref "SP6") (pin "2") (pinfunction "2_2") (pintype "passive"))
      (node (ref "T6") (pin "2") (pinfunction "M2_2") (pintype "bidirectional"))
      (node (ref "TVS6") (pin "A") (pinfunction "A_A") (pintype "passive"))
    )
    (net (code "64") (name "Net-(T7-G)") (class "Default")
      (node (ref "R7") (pin "2") (pinfunction "2_2") (pintype "passive"))
      (node (ref "T7") (pin "3") (pinfunction "G_3") (pintype "bidirectional"))
    )
    (net (code "65") (name "Net-(T7-M2)") (class "Default")
      (node (ref "S78") (pin "1") (pinfunction "1_1") (pintype "passive"))
      (node (ref "SP7") (pin "2") (pinfunction "2_2") (pintype "passive"))
      (node (ref "T7") (pin "2") (pinfunction "M2_2") (pintype "bidirectional"))
      (node (ref "TVS7") (pin "A") (pinfunction "A_A") (pintype "passive"))
    )
    (net (code "66") (name "Net-(T8-G)") (class "Default")
      (node (ref "R8") (pin "2") (pinfunction "2_2") (pintype "passive"))
      (node (ref "T8") (pin "3") (pinfunction "G_3") (pintype "bidirectional"))
    )
    (net (code "67") (name "Net-(T8-M2)") (class "Default")
      (node (ref "S78") (pin "2") (pinfunction "2_2") (pintype "passive"))
      (node (ref "SP8") (pin "2") (pinfunction "2_2") (pintype "passive"))
      (node (ref "T8") (pin "2") (pinfunction "M2_2") (pintype "bidirectional"))
      (node (ref "TVS8") (pin "A") (pinfunction "A_A") (pintype "passive"))
    )
    (net (code "68") (name "Net-(U$2-12-GPIO1)") (class "Default")
      (node (ref "JP4") (pin "12") (pinfunction "12_12") (pintype "passive"))
      (node (ref "U$2") (pin "12") (pinfunction "12-GPIO1_12") (pintype "bidirectional"))
    )
    (net (code "69") (name "Net-(U$2-14-DNC)") (class "Default")
      (node (ref "JP4") (pin "14") (pinfunction "14_14") (pintype "passive"))
      (node (ref "U$2") (pin "14") (pinfunction "14-DNC_14") (pintype "bidirectional"))
    )
    (net (code "70") (name "Net-(U$2-16-GPIO4)") (class "Default")
      (node (ref "JP4") (pin "16") (pinfunction "16_16") (pintype "passive"))
      (node (ref "U$2") (pin "16") (pinfunction "16-GPIO4_16") (pintype "bidirectional"))
    )
    (net (code "71") (name "Net-(U$2-17-DNC)") (class "Default")
      (node (ref "JP4") (pin "17") (pinfunction "17_17") (pintype "passive"))
      (node (ref "U$2") (pin "17") (pinfunction "17-DNC_17") (pintype "bidirectional"))
    )
    (net (code "72") (name "Net-(U$2-18-GPIO5)") (class "Default")
      (node (ref "JP4") (pin "18") (pinfunction "18_18") (pintype "passive"))
      (node (ref "U$2") (pin "18") (pinfunction "18-GPIO5_18") (pintype "bidirectional"))
    )
    (net (code "73") (name "Net-(U$2-19-SPI-MOSI)") (class "Default")
      (node (ref "JP4") (pin "19") (pinfunction "19_19") (pintype "passive"))
      (node (ref "U$2") (pin "19") (pinfunction "19-SPI-MOSI_19") (pintype "bidirectional"))
    )
    (net (code "74") (name "Net-(U$2-20-DNC)") (class "Default")
      (node (ref "JP4") (pin "20") (pinfunction "20_20") (pintype "passive"))
      (node (ref "U$2") (pin "20") (pinfunction "20-DNC_20") (pintype "bidirectional"))
    )
    (net (code "75") (name "Net-(U$2-21-SPI-MISO)") (class "Default")
      (node (ref "JP4") (pin "21") (pinfunction "21_21") (pintype "passive"))
      (node (ref "U$2") (pin "21") (pinfunction "21-SPI-MISO_21") (pintype "bidirectional"))
    )
    (net (code "76") (name "Net-(U$2-22-GPIO6)") (class "Default")
      (node (ref "JP4") (pin "22") (pinfunction "22_22") (pintype "passive"))
      (node (ref "U$2") (pin "22") (pinfunction "22-GPIO6_22") (pintype "bidirectional"))
    )
    (net (code "77") (name "Net-(U$2-23-SPI-SCLK)") (class "Default")
      (node (ref "JP4") (pin "23") (pinfunction "23_23") (pintype "passive"))
      (node (ref "U$2") (pin "23") (pinfunction "23-SPI-SCLK_23") (pintype "bidirectional"))
    )
    (net (code "78") (name "Net-(U$2-24-SPI-CE0-N)") (class "Default")
      (node (ref "JP4") (pin "24") (pinfunction "24_24") (pintype "passive"))
      (node (ref "U$2") (pin "24") (pinfunction "24-SPI-CE0-N_24") (pintype "bidirectional"))
    )
    (net (code "79") (name "Net-(U$2-25-DNC)") (class "Default")
      (node (ref "JP4") (pin "25") (pinfunction "25_25") (pintype "passive"))
      (node (ref "U$2") (pin "25") (pinfunction "25-DNC_25") (pintype "bidirectional"))
    )
    (net (code "80") (name "Net-(U$2-26-SPI-CE1-N)") (class "Default")
      (node (ref "JP4") (pin "26") (pinfunction "26_26") (pintype "passive"))
      (node (ref "U$2") (pin "26") (pinfunction "26-SPI-CE1-N_26") (pintype "bidirectional"))
    )
    (net (code "81") (name "Net-(U$2-27-SD)") (class "Default")
      (node (ref "JP4") (pin "27") (pinfunction "27_27") (pintype "passive"))
      (node (ref "U$2") (pin "27") (pinfunction "27-SD_27") (pintype "bidirectional"))
    )
    (net (code "82") (name "Net-(U$2-28-SC)") (class "Default")
      (node (ref "JP4") (pin "28") (pinfunction "28_28") (pintype "passive"))
      (node (ref "U$2") (pin "28") (pinfunction "28-SC_28") (pintype "bidirectional"))
    )
    (net (code "83") (name "VCC") (class "Default")
      (node (ref "74HC595") (pin "10") (pinfunction "SCL_10") (pintype "input"))
      (node (ref "74HC595") (pin "16") (pinfunction "VCC_16") (pintype "power_in"))
      (node (ref "C3") (pin "1") (pinfunction "1_1") (pintype "passive"))
      (node (ref "C5") (pin "1") (pinfunction "1_1") (pintype "passive"))
      (node (ref "EXTOUT") (pin "8") (pinfunction "8_8") (pintype "passive"))
      (node (ref "JP4") (pin "1") (pinfunction "1_1") (pintype "passive"))
      (node (ref "JP6") (pin "1") (pinfunction "1_1") (pintype "passive"))
      (node (ref "JP6") (pin "2") (pinfunction "2_2") (pintype "passive"))
      (node (ref "JP6") (pin "3") (pinfunction "3_3") (pintype "passive"))
      (node (ref "JP6") (pin "4") (pinfunction "4_4") (pintype "passive"))
      (node (ref "JP6") (pin "5") (pinfunction "5_5") (pintype "passive"))
      (node (ref "PCF8591") (pin "14") (pinfunction "VREF_14") (pintype "input"))
      (node (ref "PCF8591") (pin "16") (pinfunction "VDD_16") (pintype "power_in"))
      (node (ref "ROE") (pin "2") (pinfunction "2_2") (pintype "passive"))
      (node (ref "RP") (pin "2") (pinfunction "2_2") (pintype "passive"))
      (node (ref "U$2") (pin "1") (pinfunction "1-+3V3_1") (pintype "bidirectional"))
    )
    (net (code "84") (name "unconnected-(1307-SQW{slash}OUT-Pad7)") (class "Default")
      (node (ref "1307") (pin "7") (pinfunction "SQW/OUT_7") (pintype "bidirectional"))
    )
    (net (code "85") (name "unconnected-(PCF8591-OSC-Pad11)") (class "Default")
      (node (ref "PCF8591") (pin "11") (pinfunction "OSC_11") (pintype "input"))
    )
    (net (code "86") (name "unconnected-(T1-M2-4-Pad4)") (class "Default")
      (node (ref "T1") (pin "4") (pinfunction "M2-4_4") (pintype "bidirectional"))
    )
    (net (code "87") (name "unconnected-(T2-M2-4-Pad4)") (class "Default")
      (node (ref "T2") (pin "4") (pinfunction "M2-4_4") (pintype "bidirectional"))
    )
    (net (code "88") (name "unconnected-(T3-M2-4-Pad4)") (class "Default")
      (node (ref "T3") (pin "4") (pinfunction "M2-4_4") (pintype "bidirectional"))
    )
    (net (code "89") (name "unconnected-(T4-M2-4-Pad4)") (class "Default")
      (node (ref "T4") (pin "4") (pinfunction "M2-4_4") (pintype "bidirectional"))
    )
    (net (code "90") (name "unconnected-(T5-M2-4-Pad4)") (class "Default")
      (node (ref "T5") (pin "4") (pinfunction "M2-4_4") (pintype "bidirectional"))
    )
    (net (code "91") (name "unconnected-(T6-M2-4-Pad4)") (class "Default")
      (node (ref "T6") (pin "4") (pinfunction "M2-4_4") (pintype "bidirectional"))
    )
    (net (code "92") (name "unconnected-(T7-M2-4-Pad4)") (class "Default")
      (node (ref "T7") (pin "4") (pinfunction "M2-4_4") (pintype "bidirectional"))
    )
    (net (code "93") (name "unconnected-(T8-M2-4-Pad4)") (class "Default")
      (node (ref "T8") (pin "4") (pinfunction "M2-4_4") (pintype "bidirectional"))
    )
  )
)
